# SX1278_RADIO.net
KiCad netlist of a schematic drawn in Altium Designer
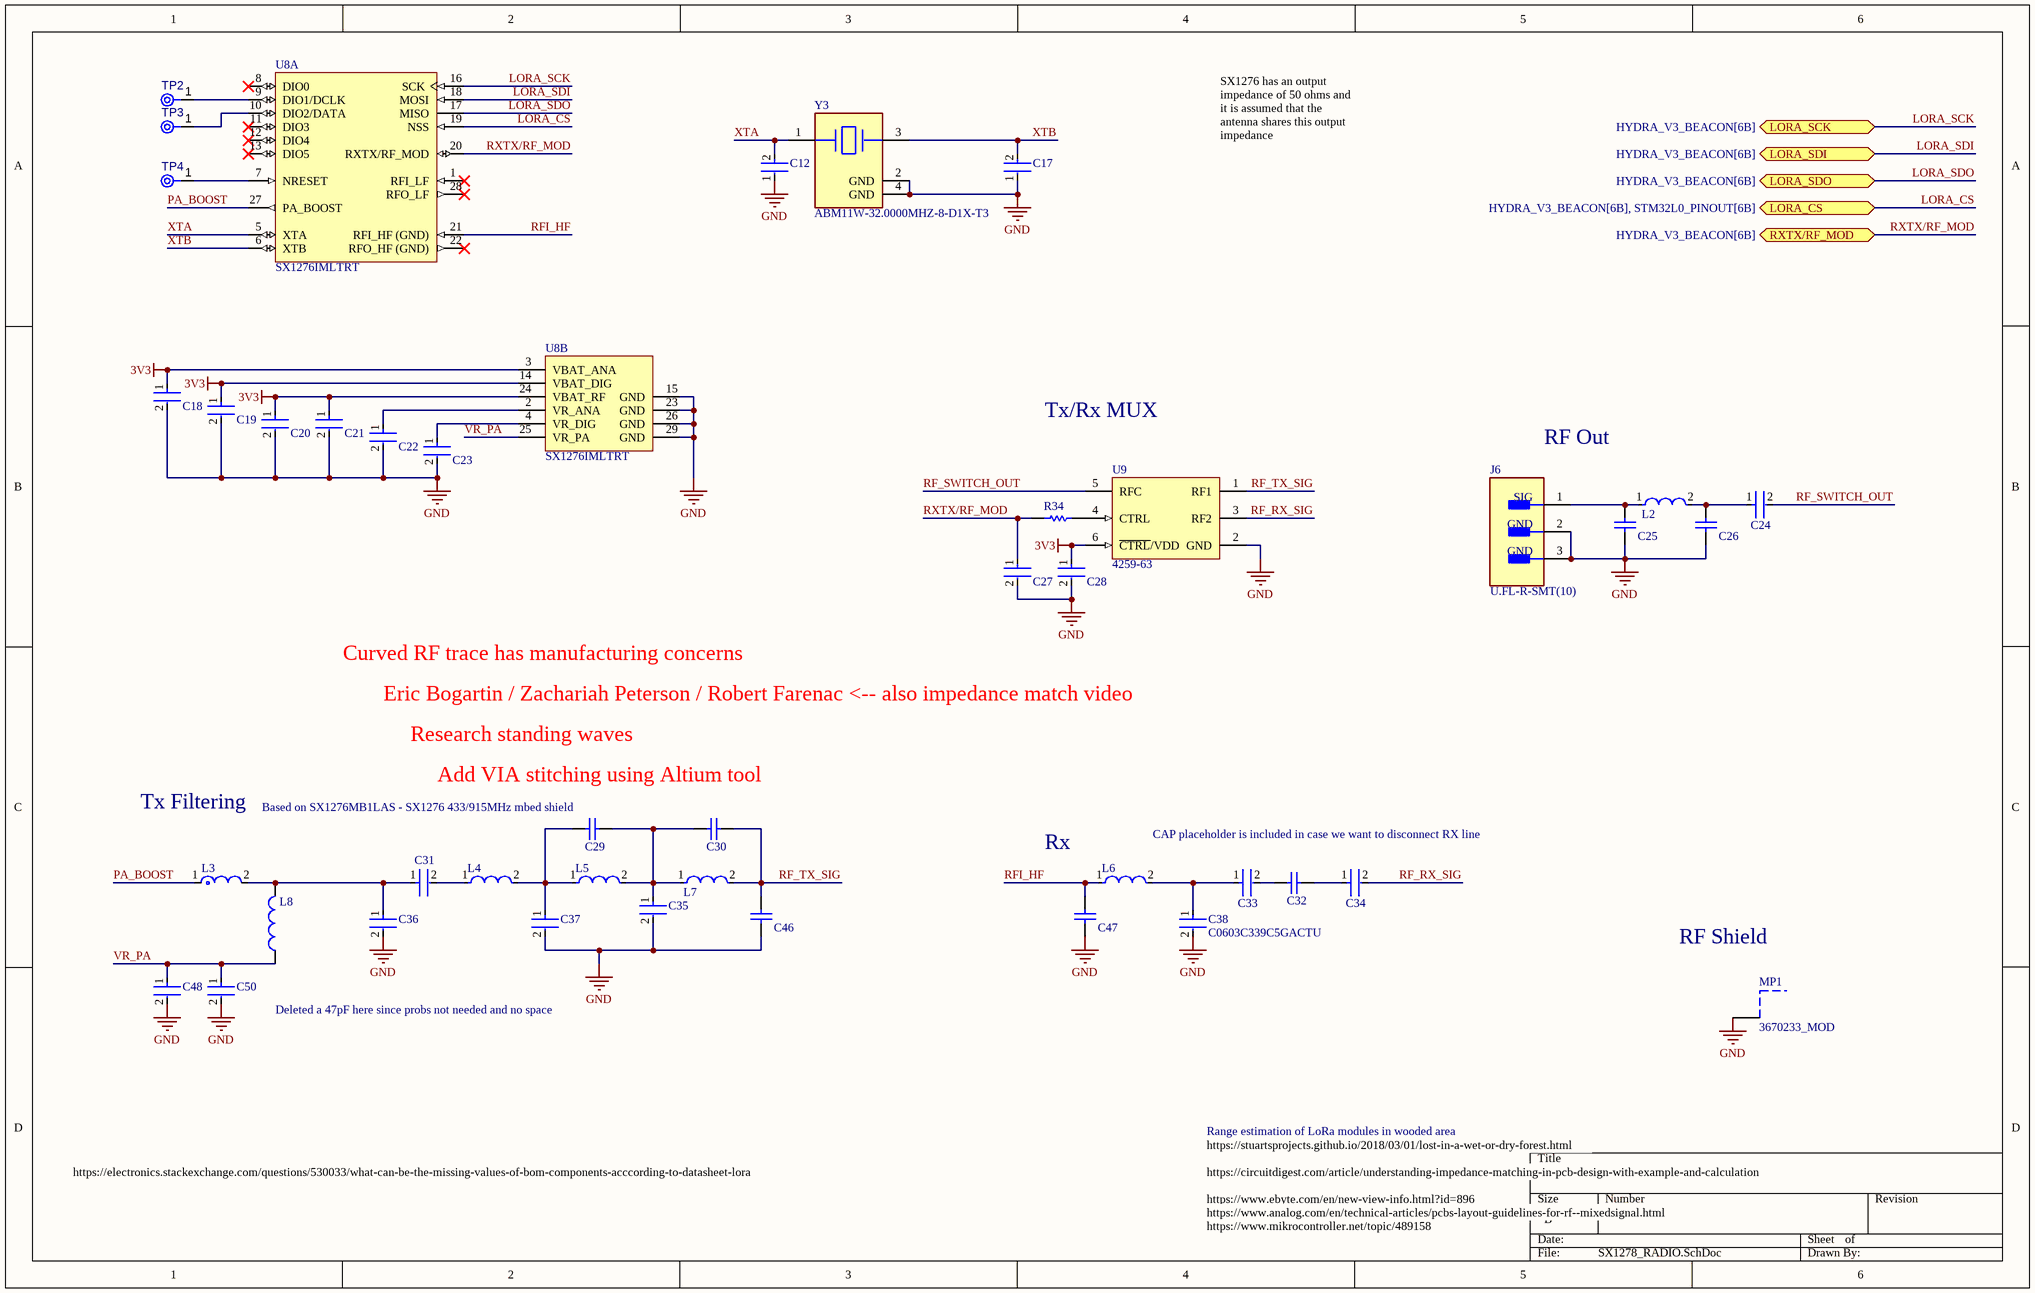
[diagram p0: SX1278_RADIO.SchDoc]

(export (version "E")
  (design (tool "Eeschema 10.0.6"))
  (components
    (comp (ref "C12")
      (value "C1608C0G1H080D080AA")
      (footprint "FP-C1608-080-0_1-IPC_A")
      (description "Multilayer Ceramic Capacitors 8pF ±0.5pF 50V C0G SMD 0603")
      (libsource (lib "Altium Content Vault") (part "236180d848d6139a670b325ea6854c9"))
    )
    (comp (ref "C17")
      (value "C1608C0G1H080D080AA")
      (footprint "FP-C1608-080-0_1-IPC_A")
      (description "Multilayer Ceramic Capacitors 8pF ±0.5pF 50V C0G SMD 0603")
      (libsource (lib "Altium Content Vault") (part "236180d848d6139a670b325ea6854c9"))
    )
    (comp (ref "C18")
      (value "C0402C104K8PACTU")
      (footprint "FP-C0402-BB-MFG")
      (description "CAP CER 0.1UF 10V X5R 0402")
      (fields (field (name "MANUFACTURER") "Kemet") (field (name "TOLERANCE") "0.1"))
      (libsource (lib "Altium Content Vault") (part "b4654b650e69147ec39a6b967a45e02"))
    )
    (comp (ref "C19")
      (value "C0402C104K8PACTU")
      (footprint "FP-C0402-BB-MFG")
      (description "CAP CER 0.1UF 10V X5R 0402")
      (fields (field (name "MANUFACTURER") "Kemet") (field (name "TOLERANCE") "0.1"))
      (libsource (lib "Altium Content Vault") (part "b4654b650e69147ec39a6b967a45e02"))
    )
    (comp (ref "C20")
      (value "C0402C104K8PACTU")
      (footprint "FP-C0402-BB-MFG")
      (description "CAP CER 0.1UF 10V X5R 0402")
      (fields (field (name "MANUFACTURER") "Kemet") (field (name "TOLERANCE") "0.1"))
      (libsource (lib "Altium Content Vault") (part "b4654b650e69147ec39a6b967a45e02"))
    )
    (comp (ref "C21")
      (value "C0402C104K8PACTU")
      (footprint "FP-C0402-BB-MFG")
      (description "CAP CER 0.1UF 10V X5R 0402")
      (fields (field (name "MANUFACTURER") "Kemet") (field (name "TOLERANCE") "0.1"))
      (libsource (lib "Altium Content Vault") (part "b4654b650e69147ec39a6b967a45e02"))
    )
    (comp (ref "C22")
      (value "C0402C104K8PACTU")
      (footprint "FP-C0402-BB-MFG")
      (description "CAP CER 0.1UF 10V X5R 0402")
      (fields (field (name "MANUFACTURER") "Kemet") (field (name "TOLERANCE") "0.1"))
      (libsource (lib "Altium Content Vault") (part "b4654b650e69147ec39a6b967a45e02"))
    )
    (comp (ref "C23")
      (value "C0402C104K8PACTU")
      (footprint "FP-C0402-BB-MFG")
      (description "CAP CER 0.1UF 10V X5R 0402")
      (fields (field (name "MANUFACTURER") "Kemet") (field (name "TOLERANCE") "0.1"))
      (libsource (lib "Altium Content Vault") (part "b4654b650e69147ec39a6b967a45e02"))
    )
    (comp (ref "C24")
      (value "C0603C470J1GACTU")
      (footprint "FP-C0603C-CF-MFG")
      (description "CAP CER 47PF 100V 5% NP0 0603")
      (fields
        (field (name "MANUFACTURER") "KEMET")
        (field (name "OCTOPART") "https://octopart.com/c0603c470j1gactu-kemet-3768219")
      )
      (libsource (lib "Altium Content Vault") (part "b4654b650e69147ec39a6b967a45e02"))
    )
    (comp (ref "C25")
      (value "0603 CAP")
      (footprint "CAPC1608X90X40ML10T20")
      (description "0pF 0603 capacitor placeholder")
      (libsource (lib "uORocketry Hardware") (part "CAP-NP-2"))
    )
    (comp (ref "C26")
      (value "0603 CAP")
      (footprint "CAPC1608X90X40ML10T20")
      (description "0pF 0603 capacitor placeholder")
      (libsource (lib "uORocketry Hardware") (part "CAP-NP-2"))
    )
    (comp (ref "C27")
      (value "C0402C104K8PACTU")
      (footprint "FP-C0402-BB-MFG")
      (description "CAP CER 0.1UF 10V X5R 0402")
      (fields (field (name "MANUFACTURER") "Kemet") (field (name "TOLERANCE") "0.1"))
      (libsource (lib "Altium Content Vault") (part "b4654b650e69147ec39a6b967a45e02"))
    )
    (comp (ref "C28")
      (value "C0402C104K8PACTU")
      (footprint "FP-C0402-BB-MFG")
      (description "CAP CER 0.1UF 10V X5R 0402")
      (fields (field (name "MANUFACTURER") "Kemet") (field (name "TOLERANCE") "0.1"))
      (libsource (lib "Altium Content Vault") (part "b4654b650e69147ec39a6b967a45e02"))
    )
    (comp (ref "C29")
      (value "0603 CAP")
      (footprint "CAPC1608X90X40ML10T20")
      (description "0pF 0603 capacitor placeholder")
      (libsource (lib "uORocketry Hardware") (part "CAP-NP-2"))
    )
    (comp (ref "C30")
      (value "0603 CAP")
      (footprint "CAPC1608X90X40ML10T20")
      (description "0pF 0603 capacitor placeholder")
      (libsource (lib "uORocketry Hardware") (part "CAP-NP-2"))
    )
    (comp (ref "C31")
      (value "C0603C220J5GACTU")
      (footprint "FP-C0603C-CF-MFG")
      (description "Cap Ceramic 22pF 50V C0G 5% SMD 0603 125°C Paper T/R")
      (fields (field (name "TOLERANCE") "0.05") (field (name "MANUFACTURER") "KEMET"))
      (libsource (lib "Altium Content Vault") (part "b4654b650e69147ec39a6b967a45e02"))
    )
    (comp (ref "C32")
      (value "0603 CAP")
      (footprint "CAPC1608X90X40ML10T20")
      (description "0pF 0603 capacitor placeholder")
      (libsource (lib "uORocketry Hardware") (part "CAP-NP-2"))
    )
    (comp (ref "C33")
      (value "C0603C470J1GACTU")
      (footprint "FP-C0603C-CF-MFG")
      (description "CAP CER 47PF 100V 5% NP0 0603")
      (fields
        (field (name "MANUFACTURER") "KEMET")
        (field (name "OCTOPART") "https://octopart.com/c0603c470j1gactu-kemet-3768219")
      )
      (libsource (lib "Altium Content Vault") (part "b4654b650e69147ec39a6b967a45e02"))
    )
    (comp (ref "C34")
      (value "C0603C470J1GACTU")
      (footprint "FP-C0603C-CF-MFG")
      (description "CAP CER 47PF 100V 5% NP0 0603")
      (fields
        (field (name "MANUFACTURER") "KEMET")
        (field (name "OCTOPART") "https://octopart.com/c0603c470j1gactu-kemet-3768219")
      )
      (libsource (lib "Altium Content Vault") (part "b4654b650e69147ec39a6b967a45e02"))
    )
    (comp (ref "C35")
      (value "C0603C339C5GACTU")
      (footprint "FP-C0603C-CF-MFG")
      (description "CAP CER 3.3PF 50V NP0 0603")
      (fields
        (field (name "TOLERANCE") "0.25 pF")
        (field (name "OCTOPART") "https://octopart.com/c0603c339c5gactu-kemet-3701205")
      )
      (libsource (lib "Altium Content Vault") (part "b4654b650e69147ec39a6b967a45e02"))
    )
    (comp (ref "C36")
      (value "C0603C829C5GACTU")
      (footprint "FP-C0603C-CF-MFG")
      (description "CAP CER 8.2PF 50V NP0 0603")
      (fields
        (field (name "OCTOPART") "https://octopart.com/c0603c829c5gactu-kemet-8375751")
        (field (name "TOLERANCE") "0.25 pF")
      )
      (libsource (lib "Altium Content Vault") (part "b4654b650e69147ec39a6b967a45e02"))
    )
    (comp (ref "C37")
      (value "06031A6R8CAT2A")
      (footprint "FP-0603-L_1_6_0_15-W_0_81-IPC_C")
      (description "General Purpose Ceramic Capacitor, 0603, 6.8pF, 0.25pF, NP0, 30ppm/°C, 100V")
      (fields (field (name "VOLTAGE") "100V"))
      (libsource (lib "Altium Content Vault") (part "02cd4be3c70576c341d710602a673aa"))
    )
    (comp (ref "C38")
      (value "C0603C339C5GACTU")
      (footprint "FP-C0603C-CF-MFG")
      (description "CAP CER 3.3PF 50V NP0 0603")
      (fields
        (field (name "TOLERANCE") "0.25 pF")
        (field (name "OCTOPART") "https://octopart.com/c0603c339c5gactu-kemet-3701205")
      )
      (libsource (lib "Altium Content Vault") (part "b4654b650e69147ec39a6b967a45e02"))
    )
    (comp (ref "C46")
      (value "0603 CAP")
      (footprint "CAPC1608X90X40ML10T20")
      (description "0pF 0603 capacitor placeholder")
      (libsource (lib "uORocketry Hardware") (part "CAP-NP-2"))
    )
    (comp (ref "C47")
      (value "0603 CAP")
      (footprint "CAPC1608X90X40ML10T20")
      (description "0pF 0603 capacitor placeholder")
      (libsource (lib "uORocketry Hardware") (part "CAP-NP-2"))
    )
    (comp (ref "C48")
      (value "C0603C103J3GACTU")
      (footprint "FP-C0603C-CF-MFG")
      (description "CAP CER 10000PF 25V 5% NP0 0603")
      (fields
        (field (name "OCTOPART") "https://octopart.com/c0603c103j3gactu-kemet-10686801")
        (field (name "MANUFACTURER") "KEMET")
      )
      (libsource (lib "Altium Content Vault") (part "b4654b650e69147ec39a6b967a45e02"))
    )
    (comp (ref "C50")
      (value "C0603C470J1GACTU")
      (footprint "FP-C0603C-CF-MFG")
      (description "CAP CER 47PF 100V 5% NP0 0603")
      (fields
        (field (name "MANUFACTURER") "KEMET")
        (field (name "OCTOPART") "https://octopart.com/c0603c470j1gactu-kemet-3768219")
      )
      (libsource (lib "Altium Content Vault") (part "b4654b650e69147ec39a6b967a45e02"))
    )
    (comp (ref "J6")
      (value "U.FL-R-SMT(10)")
      (footprint "FP-U_FL-R-SMT_10-MFG")
      (description "CONN U.FL RCPT STR 50 OHM SMD")
      (libsource (lib "Altium Content Vault") (part "eef6fde44c591823e8076210edfe12f"))
    )
    (comp (ref "L2")
      (value "0603 IND")
      (footprint "FP-LQW18AN_00-MFG")
      (description "0uH 0603 inductor placeholder")
      (libsource (lib "uORocketry Hardware") (part "725321dda6339637d4d059423bc1c3c"))
    )
    (comp (ref "L3")
      (value "LQG18HN1N5S00D")
      (footprint "FP-LQG18HH_00-IPC_B")
      (description "Multilayer type RF Inductor 1.5nH ±0.3nH 0.1Ω 1100mA 0603")
      (libsource (lib "Altium Content Vault") (part "4cc4b267dca4c8e51f7102f422741d8"))
    )
    (comp (ref "L4")
      (value "LQW18AN5N6D00D")
      (footprint "FP-LQW18AN_00-MFG")
      (description "Wire Wound RF Inductor 5.6nH ±0.5nH 750mA 0.082Ω 0603 (1608)")
      (libsource (lib "Altium Content Vault") (part "725321dda6339637d4d059423bc1c3c"))
    )
    (comp (ref "L5")
      (value "LQW18AN5N6D00D")
      (footprint "FP-LQW18AN_00-MFG")
      (description "Wire Wound RF Inductor 5.6nH ±0.5nH 750mA 0.082Ω 0603 (1608)")
      (libsource (lib "Altium Content Vault") (part "725321dda6339637d4d059423bc1c3c"))
    )
    (comp (ref "L6")
      (value "LQW18AN10NG00D")
      (footprint "FP-LQW18AN_00-MFG")
      (description "Wire Wound RF Inductor 10nH ±2% 650mA 0.11Ω 0603 (1608)")
      (fields (field (name "TOLERANCE") "2%"))
      (libsource (lib "Altium Content Vault") (part "725321dda6339637d4d059423bc1c3c"))
    )
    (comp (ref "L7")
      (value "0603 IND")
      (footprint "FP-LQW18AN_00-MFG")
      (description "0uH 0603 inductor placeholder")
      (libsource (lib "uORocketry Hardware") (part "725321dda6339637d4d059423bc1c3c"))
    )
    (comp (ref "L8")
      (value "B82496C3330J")
      (footprint "INDC1608X90X30LL10T20")
      (fields (field (name "MANUFACTURER") "EPCOS-(TDK)") (field (name "TOLERANCE") "±5%"))
      (libsource (lib "Altium Content Vault") (part "IND-2"))
    )
    (comp (ref "MP1")
      (value "3670233_MOD")
      (footprint "3670233")
      (libsource (lib "uORocketry Hardware") (part "WE-SHC"))
    )
    (comp (ref "R34")
      (value "ERJ-3EKF1001V")
      (footprint "RESC1608X55X30LL15T15")
      (fields (field (name "MANUFACTURER") "Panasonic"))
      (libsource (lib "Altium Content Vault") (part "RES"))
    )
    (comp (ref "TP2")
      (value "TPAD6R")
      (footprint "TP06R")
      (description "0.6mm round")
      (libsource (lib "uORocketry Hardware") (part "CMP-001-0001-4"))
    )
    (comp (ref "TP3")
      (value "TPAD6R")
      (footprint "TP06R")
      (description "0.6mm round")
      (libsource (lib "uORocketry Hardware") (part "CMP-001-0001-4"))
    )
    (comp (ref "TP4")
      (value "TPAD6R")
      (footprint "TP06R")
      (description "0.6mm round")
      (libsource (lib "uORocketry Hardware") (part "CMP-001-0001-4"))
    )
    (comp (ref "U8")
      (value "SX1276IMLTRT")
      (footprint "SMTC-QFN-28_V")
      (description "Low Power Long Range Transceiver, 137 to 1020 MHz, -40 to 85 degC, 28-Pin QFN, RoHS, Tape and Reel")
      (fields (field (name "MANUFACTURER") "Semtech"))
      (libsource (lib "Altium Content Vault") (part "SMTC-SX127X-QFN-28"))
    )
    (comp (ref "U9")
      (value "4259-63")
      (footprint "PERE-SC-70-6_M")
      (description "IC RF Switch SPDT, 50 Ohm, 6-Pin SC70, RoHS, Tape and Reel")
      (fields (field (name "MANUFACTURER") "Peregrine Semiconductor"))
      (libsource (lib "Altium Content Vault") (part "PERE-PE4259-6"))
    )
    (comp (ref "Y3")
      (value "ABM11W-32.0000MHZ-8-D1X-T3")
      (footprint "FP-ABM11W-MFG")
      (description "Crystal 32MHz ±10ppm 8pF SMD-4 2mm x 1.6mm")
      (libsource (lib "Altium Content Vault") (part "5fba445d8d5f95165d6b3865099b029"))
    )
  )
  (nets
    (net (code "1") (name "/LORA_CS") (class "Default")
      (node (ref "U8") (pin "19") (pinfunction "NSS_19") (pintype "input"))
    )
    (net (code "2") (name "/LORA_SCK") (class "Default")
      (node (ref "U8") (pin "16") (pinfunction "SCK_16") (pintype "input"))
    )
    (net (code "3") (name "/LORA_SDI") (class "Default")
      (node (ref "U8") (pin "18") (pinfunction "MOSI_18") (pintype "input"))
    )
    (net (code "4") (name "/LORA_SDO") (class "Default")
      (node (ref "U8") (pin "17") (pinfunction "MISO_17") (pintype "tri_state"))
    )
    (net (code "5") (name "/PA_BOOST") (class "Default")
      (node (ref "L3") (pin "1") (pinfunction "1_1") (pintype "passive"))
      (node (ref "U8") (pin "27") (pinfunction "PA_BOOST_27") (pintype "output"))
    )
    (net (code "6") (name "/RFI_HF") (class "Default")
      (node (ref "C47") (pin "2") (pinfunction "2_2") (pintype "passive"))
      (node (ref "L6") (pin "1") (pinfunction "1_1") (pintype "passive"))
      (node (ref "U8") (pin "21") (pinfunction "RFI_HF_(GND)_21") (pintype "input"))
    )
    (net (code "7") (name "/RF_RX_SIG") (class "Default")
      (node (ref "C34") (pin "2") (pinfunction "2_2") (pintype "passive"))
      (node (ref "U9") (pin "3") (pinfunction "RF2_3") (pintype "passive"))
    )
    (net (code "8") (name "/RF_SWITCH_OUT") (class "Default")
      (node (ref "C24") (pin "2") (pinfunction "2_2") (pintype "passive"))
      (node (ref "U9") (pin "5") (pinfunction "RFC_5") (pintype "passive"))
    )
    (net (code "9") (name "/RF_TX_SIG") (class "Default")
      (node (ref "C30") (pin "2") (pinfunction "2_2") (pintype "passive"))
      (node (ref "C46") (pin "2") (pinfunction "2_2") (pintype "passive"))
      (node (ref "L7") (pin "2") (pinfunction "2_2") (pintype "passive"))
      (node (ref "U9") (pin "1") (pinfunction "RF1_1") (pintype "passive"))
    )
    (net (code "10") (name "/RXTX{slash}RF_MOD") (class "Default")
      (node (ref "C27") (pin "1") (pinfunction "1_1") (pintype "passive"))
      (node (ref "R34") (pin "2") (pinfunction "2_2") (pintype "passive"))
      (node (ref "U8") (pin "20") (pinfunction "RXTX/RF_MOD_20") (pintype "bidirectional"))
    )
    (net (code "11") (name "/VR_PA") (class "Default")
      (node (ref "C48") (pin "1") (pinfunction "1_1") (pintype "passive"))
      (node (ref "C50") (pin "1") (pinfunction "1_1") (pintype "passive"))
      (node (ref "L8") (pin "1") (pinfunction "1_1") (pintype "passive"))
      (node (ref "U8") (pin "25") (pinfunction "VR_PA_25") (pintype "power_in"))
    )
    (net (code "12") (name "/XTA") (class "Default")
      (node (ref "C12") (pin "2") (pinfunction "2_2") (pintype "passive"))
      (node (ref "U8") (pin "5") (pinfunction "XTA_5") (pintype "bidirectional"))
      (node (ref "Y3") (pin "1") (pinfunction "1_1") (pintype "passive"))
    )
    (net (code "13") (name "/XTB") (class "Default")
      (node (ref "C17") (pin "2") (pinfunction "2_2") (pintype "passive"))
      (node (ref "U8") (pin "6") (pinfunction "XTB_6") (pintype "bidirectional"))
      (node (ref "Y3") (pin "3") (pinfunction "3_3") (pintype "passive"))
    )
    (net (code "14") (name "3V3") (class "Default")
      (node (ref "C18") (pin "1") (pinfunction "1_1") (pintype "passive"))
      (node (ref "C19") (pin "1") (pinfunction "1_1") (pintype "passive"))
      (node (ref "C20") (pin "1") (pinfunction "1_1") (pintype "passive"))
      (node (ref "C21") (pin "1") (pinfunction "1_1") (pintype "passive"))
      (node (ref "C28") (pin "1") (pinfunction "1_1") (pintype "passive"))
      (node (ref "U8") (pin "14") (pinfunction "VBAT_DIG_14") (pintype "power_in"))
      (node (ref "U8") (pin "24") (pinfunction "VBAT_RF_24") (pintype "power_in"))
      (node (ref "U8") (pin "3") (pinfunction "VBAT_ANA_3") (pintype "power_in"))
      (node (ref "U9") (pin "6") (pinfunction "~{CTRL}/VDD_6") (pintype "input"))
    )
    (net (code "15") (name "GND") (class "Default")
      (node (ref "C12") (pin "1") (pinfunction "1_1") (pintype "passive"))
      (node (ref "C17") (pin "1") (pinfunction "1_1") (pintype "passive"))
      (node (ref "C18") (pin "2") (pinfunction "2_2") (pintype "passive"))
      (node (ref "C19") (pin "2") (pinfunction "2_2") (pintype "passive"))
      (node (ref "C20") (pin "2") (pinfunction "2_2") (pintype "passive"))
      (node (ref "C21") (pin "2") (pinfunction "2_2") (pintype "passive"))
      (node (ref "C22") (pin "2") (pinfunction "2_2") (pintype "passive"))
      (node (ref "C23") (pin "2") (pinfunction "2_2") (pintype "passive"))
      (node (ref "C25") (pin "1") (pinfunction "1_1") (pintype "passive"))
      (node (ref "C26") (pin "1") (pinfunction "1_1") (pintype "passive"))
      (node (ref "C27") (pin "2") (pinfunction "2_2") (pintype "passive"))
      (node (ref "C28") (pin "2") (pinfunction "2_2") (pintype "passive"))
      (node (ref "C35") (pin "2") (pinfunction "2_2") (pintype "passive"))
      (node (ref "C36") (pin "2") (pinfunction "2_2") (pintype "passive"))
      (node (ref "C37") (pin "2") (pinfunction "2_2") (pintype "passive"))
      (node (ref "C38") (pin "2") (pinfunction "2_2") (pintype "passive"))
      (node (ref "C46") (pin "1") (pinfunction "1_1") (pintype "passive"))
      (node (ref "C47") (pin "1") (pinfunction "1_1") (pintype "passive"))
      (node (ref "C48") (pin "2") (pinfunction "2_2") (pintype "passive"))
      (node (ref "C50") (pin "2") (pinfunction "2_2") (pintype "passive"))
      (node (ref "J6") (pin "2") (pinfunction "GND_2") (pintype "power_in"))
      (node (ref "J6") (pin "3") (pinfunction "GND_3") (pintype "power_in"))
      (node (ref "MP1") (pin "1") (pinfunction "1_1") (pintype "passive"))
      (node (ref "U8") (pin "15") (pinfunction "GND_15") (pintype "power_in"))
      (node (ref "U8") (pin "23") (pinfunction "GND_23") (pintype "power_in"))
      (node (ref "U8") (pin "26") (pinfunction "GND_26") (pintype "power_in"))
      (node (ref "U8") (pin "29") (pinfunction "GND_29") (pintype "power_in"))
      (node (ref "U9") (pin "2") (pinfunction "GND_2") (pintype "power_in"))
      (node (ref "Y3") (pin "2") (pinfunction "GND_2") (pintype "power_in"))
      (node (ref "Y3") (pin "4") (pinfunction "GND_4") (pintype "power_in"))
    )
    (net (code "16") (name "Net-(C24-Pad1)") (class "Default")
      (node (ref "C24") (pin "1") (pinfunction "1_1") (pintype "passive"))
      (node (ref "C26") (pin "2") (pinfunction "2_2") (pintype "passive"))
      (node (ref "L2") (pin "2") (pinfunction "2_2") (pintype "passive"))
    )
    (net (code "17") (name "Net-(C29-Pad1)") (class "Default")
      (node (ref "C29") (pin "1") (pinfunction "1_1") (pintype "passive"))
      (node (ref "C37") (pin "1") (pinfunction "1_1") (pintype "passive"))
      (node (ref "L4") (pin "2") (pinfunction "2_2") (pintype "passive"))
      (node (ref "L5") (pin "1") (pinfunction "1_1") (pintype "passive"))
    )
    (net (code "18") (name "Net-(C29-Pad2)") (class "Default")
      (node (ref "C29") (pin "2") (pinfunction "2_2") (pintype "passive"))
      (node (ref "C30") (pin "1") (pinfunction "1_1") (pintype "passive"))
      (node (ref "C35") (pin "1") (pinfunction "1_1") (pintype "passive"))
      (node (ref "L5") (pin "2") (pinfunction "2_2") (pintype "passive"))
      (node (ref "L7") (pin "1") (pinfunction "1_1") (pintype "passive"))
    )
    (net (code "19") (name "Net-(C31-Pad1)") (class "Default")
      (node (ref "C31") (pin "1") (pinfunction "1_1") (pintype "passive"))
      (node (ref "C36") (pin "1") (pinfunction "1_1") (pintype "passive"))
      (node (ref "L3") (pin "2") (pinfunction "2_2") (pintype "passive"))
      (node (ref "L8") (pin "2") (pinfunction "2_2") (pintype "passive"))
    )
    (net (code "20") (name "Net-(C31-Pad2)") (class "Default")
      (node (ref "C31") (pin "2") (pinfunction "2_2") (pintype "passive"))
      (node (ref "L4") (pin "1") (pinfunction "1_1") (pintype "passive"))
    )
    (net (code "21") (name "Net-(C32-Pad1)") (class "Default")
      (node (ref "C32") (pin "1") (pinfunction "1_1") (pintype "passive"))
      (node (ref "C33") (pin "2") (pinfunction "2_2") (pintype "passive"))
    )
    (net (code "22") (name "Net-(C32-Pad2)") (class "Default")
      (node (ref "C32") (pin "2") (pinfunction "2_2") (pintype "passive"))
      (node (ref "C34") (pin "1") (pinfunction "1_1") (pintype "passive"))
    )
    (net (code "23") (name "Net-(C33-Pad1)") (class "Default")
      (node (ref "C33") (pin "1") (pinfunction "1_1") (pintype "passive"))
      (node (ref "C38") (pin "1") (pinfunction "1_1") (pintype "passive"))
      (node (ref "L6") (pin "2") (pinfunction "2_2") (pintype "passive"))
    )
    (net (code "24") (name "Net-(J6-SIG)") (class "Default")
      (node (ref "C25") (pin "2") (pinfunction "2_2") (pintype "passive"))
      (node (ref "J6") (pin "1") (pinfunction "SIG_1") (pintype "passive"))
      (node (ref "L2") (pin "1") (pinfunction "1_1") (pintype "passive"))
    )
    (net (code "25") (name "Net-(TP2-TP)") (class "Default")
      (node (ref "TP2") (pin "1") (pinfunction "TP_1") (pintype "passive"))
      (node (ref "U8") (pin "9") (pinfunction "DIO1/DCLK_9") (pintype "bidirectional"))
    )
    (net (code "26") (name "Net-(TP3-TP)") (class "Default")
      (node (ref "TP3") (pin "1") (pinfunction "TP_1") (pintype "passive"))
      (node (ref "U8") (pin "10") (pinfunction "DIO2/DATA_10") (pintype "bidirectional"))
    )
    (net (code "27") (name "Net-(TP4-TP)") (class "Default")
      (node (ref "TP4") (pin "1") (pinfunction "TP_1") (pintype "passive"))
      (node (ref "U8") (pin "7") (pinfunction "NRESET_7") (pintype "input"))
    )
    (net (code "28") (name "Net-(U8B-VR_ANA)") (class "Default")
      (node (ref "C22") (pin "1") (pinfunction "1_1") (pintype "passive"))
      (node (ref "U8") (pin "2") (pinfunction "VR_ANA_2") (pintype "power_in"))
    )
    (net (code "29") (name "Net-(U8B-VR_DIG)") (class "Default")
      (node (ref "C23") (pin "1") (pinfunction "1_1") (pintype "passive"))
      (node (ref "U8") (pin "4") (pinfunction "VR_DIG_4") (pintype "power_in"))
    )
    (net (code "30") (name "Net-(U9-CTRL)") (class "Default")
      (node (ref "R34") (pin "1") (pinfunction "1_1") (pintype "passive"))
      (node (ref "U9") (pin "4") (pinfunction "CTRL_4") (pintype "input"))
    )
    (net (code "31") (name "unconnected-(U8A-DIO0-Pad8)") (class "Default")
      (node (ref "U8") (pin "8") (pinfunction "DIO0_8") (pintype "bidirectional+no_connect"))
    )
    (net (code "32") (name "unconnected-(U8A-DIO3-Pad11)") (class "Default")
      (node (ref "U8") (pin "11") (pinfunction "DIO3_11") (pintype "bidirectional+no_connect"))
    )
    (net (code "33") (name "unconnected-(U8A-DIO4-Pad12)") (class "Default")
      (node (ref "U8") (pin "12") (pinfunction "DIO4_12") (pintype "bidirectional+no_connect"))
    )
    (net (code "34") (name "unconnected-(U8A-DIO5-Pad13)") (class "Default")
      (node (ref "U8") (pin "13") (pinfunction "DIO5_13") (pintype "bidirectional+no_connect"))
    )
    (net (code "35") (name "unconnected-(U8A-RFI_LF-Pad1)") (class "Default")
      (node (ref "U8") (pin "1") (pinfunction "RFI_LF_1") (pintype "input+no_connect"))
    )
    (net (code "36") (name "unconnected-(U8A-RFO_HF_(GND)-Pad22)") (class "Default")
      (node (ref "U8") (pin "22") (pinfunction "RFO_HF_(GND)_22") (pintype "output+no_connect"))
    )
    (net (code "37") (name "unconnected-(U8A-RFO_LF-Pad28)") (class "Default")
      (node (ref "U8") (pin "28") (pinfunction "RFO_LF_28") (pintype "output+no_connect"))
    )
  )
)
